# QREx16.net
KiCad netlist of a schematic drawn in EAGLE
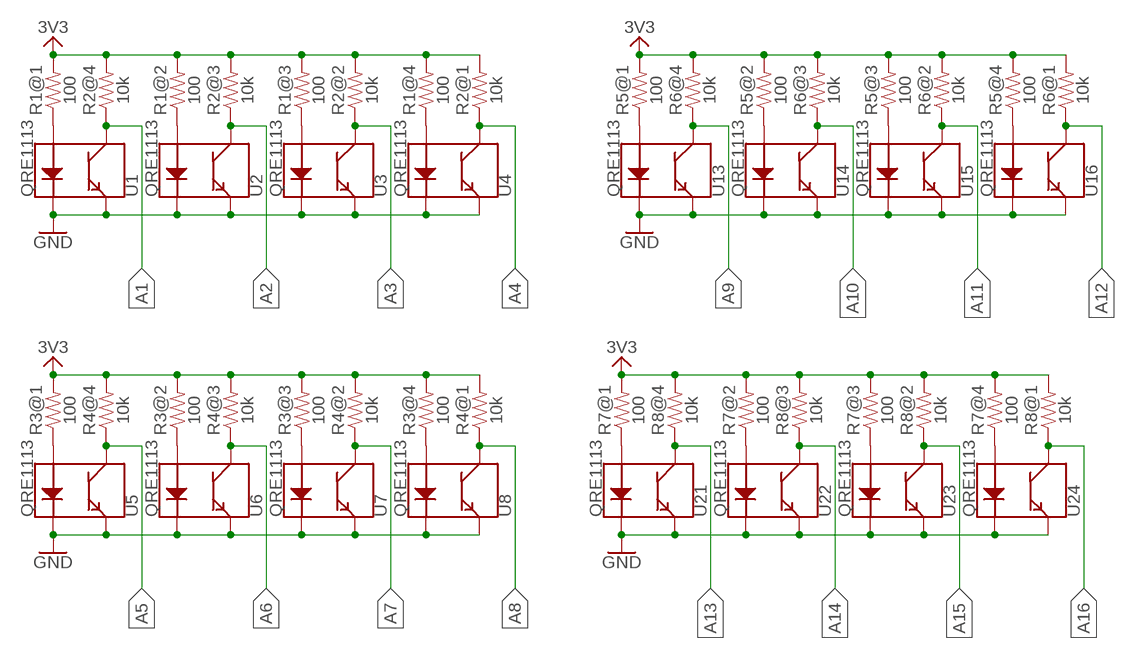
[diagram p0: schematic, sheet 1]

(export (version "E")
  (design (tool "Eeschema 10.0.6"))
  (components
    (comp (ref "R1")
      (value "100")
      (footprint "eagle-import:RESCAF80P320X160X60-8N")
      (libsource (lib "eagle-import") (part "RESISTOR_ARRAY_1206_SEPARATE"))
    )
    (comp (ref "R2")
      (value "10k")
      (footprint "eagle-import:RESCAF80P320X160X60-8N")
      (libsource (lib "eagle-import") (part "RESISTOR_ARRAY_1206_SEPARATE"))
    )
    (comp (ref "R3")
      (value "100")
      (footprint "eagle-import:RESCAF80P320X160X60-8N")
      (libsource (lib "eagle-import") (part "RESISTOR_ARRAY_1206_SEPARATE"))
    )
    (comp (ref "R4")
      (value "10k")
      (footprint "eagle-import:RESCAF80P320X160X60-8N")
      (libsource (lib "eagle-import") (part "RESISTOR_ARRAY_1206_SEPARATE"))
    )
    (comp (ref "R5")
      (value "100")
      (footprint "eagle-import:RESCAF80P320X160X60-8N")
      (libsource (lib "eagle-import") (part "RESISTOR_ARRAY_1206_SEPARATE"))
    )
    (comp (ref "R6")
      (value "10k")
      (footprint "eagle-import:RESCAF80P320X160X60-8N")
      (libsource (lib "eagle-import") (part "RESISTOR_ARRAY_1206_SEPARATE"))
    )
    (comp (ref "R7")
      (value "100")
      (footprint "eagle-import:RESCAF80P320X160X60-8N")
      (libsource (lib "eagle-import") (part "RESISTOR_ARRAY_1206_SEPARATE"))
    )
    (comp (ref "R8")
      (value "10k")
      (footprint "eagle-import:RESCAF80P320X160X60-8N")
      (libsource (lib "eagle-import") (part "RESISTOR_ARRAY_1206_SEPARATE"))
    )
    (comp (ref "U1")
      (value "QRE1113")
      (footprint "eagle-import:QRE1113-W")
      (libsource (lib "eagle-import") (part "QRE1113SMD-W"))
    )
    (comp (ref "U2")
      (value "QRE1113")
      (footprint "eagle-import:QRE1113-W")
      (libsource (lib "eagle-import") (part "QRE1113SMD-W"))
    )
    (comp (ref "U3")
      (value "QRE1113")
      (footprint "eagle-import:QRE1113-W")
      (libsource (lib "eagle-import") (part "QRE1113SMD-W"))
    )
    (comp (ref "U4")
      (value "QRE1113")
      (footprint "eagle-import:QRE1113-W")
      (libsource (lib "eagle-import") (part "QRE1113SMD-W"))
    )
    (comp (ref "U5")
      (value "QRE1113")
      (footprint "eagle-import:QRE1113-W")
      (libsource (lib "eagle-import") (part "QRE1113SMD-W"))
    )
    (comp (ref "U6")
      (value "QRE1113")
      (footprint "eagle-import:QRE1113-W")
      (libsource (lib "eagle-import") (part "QRE1113SMD-W"))
    )
    (comp (ref "U7")
      (value "QRE1113")
      (footprint "eagle-import:QRE1113-W")
      (libsource (lib "eagle-import") (part "QRE1113SMD-W"))
    )
    (comp (ref "U8")
      (value "QRE1113")
      (footprint "eagle-import:QRE1113-W")
      (libsource (lib "eagle-import") (part "QRE1113SMD-W"))
    )
    (comp (ref "U13")
      (value "QRE1113")
      (footprint "eagle-import:QRE1113-W")
      (libsource (lib "eagle-import") (part "QRE1113SMD-W"))
    )
    (comp (ref "U14")
      (value "QRE1113")
      (footprint "eagle-import:QRE1113-W")
      (libsource (lib "eagle-import") (part "QRE1113SMD-W"))
    )
    (comp (ref "U15")
      (value "QRE1113")
      (footprint "eagle-import:QRE1113-W")
      (libsource (lib "eagle-import") (part "QRE1113SMD-W"))
    )
    (comp (ref "U16")
      (value "QRE1113")
      (footprint "eagle-import:QRE1113-W")
      (libsource (lib "eagle-import") (part "QRE1113SMD-W"))
    )
    (comp (ref "U21")
      (value "QRE1113")
      (footprint "eagle-import:QRE1113-W")
      (libsource (lib "eagle-import") (part "QRE1113SMD-W"))
    )
    (comp (ref "U22")
      (value "QRE1113")
      (footprint "eagle-import:QRE1113-W")
      (libsource (lib "eagle-import") (part "QRE1113SMD-W"))
    )
    (comp (ref "U23")
      (value "QRE1113")
      (footprint "eagle-import:QRE1113-W")
      (libsource (lib "eagle-import") (part "QRE1113SMD-W"))
    )
    (comp (ref "U24")
      (value "QRE1113")
      (footprint "eagle-import:QRE1113-W")
      (libsource (lib "eagle-import") (part "QRE1113SMD-W"))
    )
  )
  (nets
    (net (code "1") (name "A1") (class "Default")
      (node (ref "R2") (pin "4") (pinfunction "1_4") (pintype "passive"))
      (node (ref "U1") (pin "3") (pinfunction "C_3") (pintype "bidirectional"))
    )
    (net (code "2") (name "A2") (class "Default")
      (node (ref "R2") (pin "3") (pinfunction "1_3") (pintype "passive"))
      (node (ref "U2") (pin "3") (pinfunction "C_3") (pintype "bidirectional"))
    )
    (net (code "3") (name "A3") (class "Default")
      (node (ref "R2") (pin "2") (pinfunction "1_2") (pintype "passive"))
      (node (ref "U3") (pin "3") (pinfunction "C_3") (pintype "bidirectional"))
    )
    (net (code "4") (name "A4") (class "Default")
      (node (ref "R2") (pin "1") (pinfunction "1_1") (pintype "passive"))
      (node (ref "U4") (pin "3") (pinfunction "C_3") (pintype "bidirectional"))
    )
    (net (code "5") (name "A5") (class "Default")
      (node (ref "R4") (pin "4") (pinfunction "1_4") (pintype "passive"))
      (node (ref "U5") (pin "3") (pinfunction "C_3") (pintype "bidirectional"))
    )
    (net (code "6") (name "A6") (class "Default")
      (node (ref "R4") (pin "3") (pinfunction "1_3") (pintype "passive"))
      (node (ref "U6") (pin "3") (pinfunction "C_3") (pintype "bidirectional"))
    )
    (net (code "7") (name "A7") (class "Default")
      (node (ref "R4") (pin "2") (pinfunction "1_2") (pintype "passive"))
      (node (ref "U7") (pin "3") (pinfunction "C_3") (pintype "bidirectional"))
    )
    (net (code "8") (name "A8") (class "Default")
      (node (ref "R4") (pin "1") (pinfunction "1_1") (pintype "passive"))
      (node (ref "U8") (pin "3") (pinfunction "C_3") (pintype "bidirectional"))
    )
    (net (code "9") (name "A9") (class "Default")
      (node (ref "R6") (pin "4") (pinfunction "1_4") (pintype "passive"))
      (node (ref "U13") (pin "3") (pinfunction "C_3") (pintype "bidirectional"))
    )
    (net (code "10") (name "A10") (class "Default")
      (node (ref "R6") (pin "3") (pinfunction "1_3") (pintype "passive"))
      (node (ref "U14") (pin "3") (pinfunction "C_3") (pintype "bidirectional"))
    )
    (net (code "11") (name "A11") (class "Default")
      (node (ref "R6") (pin "2") (pinfunction "1_2") (pintype "passive"))
      (node (ref "U15") (pin "3") (pinfunction "C_3") (pintype "bidirectional"))
    )
    (net (code "12") (name "A12") (class "Default")
      (node (ref "R6") (pin "1") (pinfunction "1_1") (pintype "passive"))
      (node (ref "U16") (pin "3") (pinfunction "C_3") (pintype "bidirectional"))
    )
    (net (code "13") (name "A13") (class "Default")
      (node (ref "R8") (pin "4") (pinfunction "1_4") (pintype "passive"))
      (node (ref "U21") (pin "3") (pinfunction "C_3") (pintype "bidirectional"))
    )
    (net (code "14") (name "A14") (class "Default")
      (node (ref "R8") (pin "3") (pinfunction "1_3") (pintype "passive"))
      (node (ref "U22") (pin "3") (pinfunction "C_3") (pintype "bidirectional"))
    )
    (net (code "15") (name "A15") (class "Default")
      (node (ref "R8") (pin "2") (pinfunction "1_2") (pintype "passive"))
      (node (ref "U23") (pin "3") (pinfunction "C_3") (pintype "bidirectional"))
    )
    (net (code "16") (name "A16") (class "Default")
      (node (ref "R8") (pin "1") (pinfunction "1_1") (pintype "passive"))
      (node (ref "U24") (pin "3") (pinfunction "C_3") (pintype "bidirectional"))
    )
    (net (code "17") (name "Net-(R1B-1)") (class "Default")
      (node (ref "R1") (pin "2") (pinfunction "1_2") (pintype "passive"))
      (node (ref "U2") (pin "1") (pinfunction "A_1") (pintype "bidirectional"))
    )
    (net (code "18") (name "Net-(R1C-1)") (class "Default")
      (node (ref "R1") (pin "3") (pinfunction "1_3") (pintype "passive"))
      (node (ref "U3") (pin "1") (pinfunction "A_1") (pintype "bidirectional"))
    )
    (net (code "19") (name "Net-(R1D-1)") (class "Default")
      (node (ref "R1") (pin "4") (pinfunction "1_4") (pintype "passive"))
      (node (ref "U4") (pin "1") (pinfunction "A_1") (pintype "bidirectional"))
    )
    (net (code "20") (name "Net-(R3B-1)") (class "Default")
      (node (ref "R3") (pin "2") (pinfunction "1_2") (pintype "passive"))
      (node (ref "U6") (pin "1") (pinfunction "A_1") (pintype "bidirectional"))
    )
    (net (code "21") (name "Net-(R3C-1)") (class "Default")
      (node (ref "R3") (pin "3") (pinfunction "1_3") (pintype "passive"))
      (node (ref "U7") (pin "1") (pinfunction "A_1") (pintype "bidirectional"))
    )
    (net (code "22") (name "Net-(R3D-1)") (class "Default")
      (node (ref "R3") (pin "4") (pinfunction "1_4") (pintype "passive"))
      (node (ref "U8") (pin "1") (pinfunction "A_1") (pintype "bidirectional"))
    )
    (net (code "23") (name "Net-(R5B-1)") (class "Default")
      (node (ref "R5") (pin "2") (pinfunction "1_2") (pintype "passive"))
      (node (ref "U14") (pin "1") (pinfunction "A_1") (pintype "bidirectional"))
    )
    (net (code "24") (name "Net-(R5C-1)") (class "Default")
      (node (ref "R5") (pin "3") (pinfunction "1_3") (pintype "passive"))
      (node (ref "U15") (pin "1") (pinfunction "A_1") (pintype "bidirectional"))
    )
    (net (code "25") (name "Net-(R5D-1)") (class "Default")
      (node (ref "R5") (pin "4") (pinfunction "1_4") (pintype "passive"))
      (node (ref "U16") (pin "1") (pinfunction "A_1") (pintype "bidirectional"))
    )
    (net (code "26") (name "Net-(R7B-1)") (class "Default")
      (node (ref "R7") (pin "2") (pinfunction "1_2") (pintype "passive"))
      (node (ref "U22") (pin "1") (pinfunction "A_1") (pintype "bidirectional"))
    )
    (net (code "27") (name "Net-(R7C-1)") (class "Default")
      (node (ref "R7") (pin "3") (pinfunction "1_3") (pintype "passive"))
      (node (ref "U23") (pin "1") (pinfunction "A_1") (pintype "bidirectional"))
    )
    (net (code "28") (name "Net-(R7D-1)") (class "Default")
      (node (ref "R7") (pin "4") (pinfunction "1_4") (pintype "passive"))
      (node (ref "U24") (pin "1") (pinfunction "A_1") (pintype "bidirectional"))
    )
    (net (code "29") (name "Net-(U1-A)") (class "Default")
      (node (ref "R1") (pin "1") (pinfunction "1_1") (pintype "passive"))
      (node (ref "U1") (pin "1") (pinfunction "A_1") (pintype "bidirectional"))
    )
    (net (code "30") (name "Net-(U5-A)") (class "Default")
      (node (ref "R3") (pin "1") (pinfunction "1_1") (pintype "passive"))
      (node (ref "U5") (pin "1") (pinfunction "A_1") (pintype "bidirectional"))
    )
    (net (code "31") (name "Net-(U13-A)") (class "Default")
      (node (ref "R5") (pin "1") (pinfunction "1_1") (pintype "passive"))
      (node (ref "U13") (pin "1") (pinfunction "A_1") (pintype "bidirectional"))
    )
    (net (code "32") (name "Net-(U21-A)") (class "Default")
      (node (ref "R7") (pin "1") (pinfunction "1_1") (pintype "passive"))
      (node (ref "U21") (pin "1") (pinfunction "A_1") (pintype "bidirectional"))
    )
    (net (code "33") (name "SUPPLY_3.3V") (class "Default")
      (node (ref "R1") (pin "5") (pinfunction "2_5") (pintype "passive"))
      (node (ref "R1") (pin "6") (pinfunction "2_6") (pintype "passive"))
      (node (ref "R1") (pin "7") (pinfunction "2_7") (pintype "passive"))
      (node (ref "R1") (pin "8") (pinfunction "2_8") (pintype "passive"))
      (node (ref "R2") (pin "5") (pinfunction "2_5") (pintype "passive"))
      (node (ref "R2") (pin "6") (pinfunction "2_6") (pintype "passive"))
      (node (ref "R2") (pin "7") (pinfunction "2_7") (pintype "passive"))
      (node (ref "R2") (pin "8") (pinfunction "2_8") (pintype "passive"))
      (node (ref "R3") (pin "5") (pinfunction "2_5") (pintype "passive"))
      (node (ref "R3") (pin "6") (pinfunction "2_6") (pintype "passive"))
      (node (ref "R3") (pin "7") (pinfunction "2_7") (pintype "passive"))
      (node (ref "R3") (pin "8") (pinfunction "2_8") (pintype "passive"))
      (node (ref "R4") (pin "5") (pinfunction "2_5") (pintype "passive"))
      (node (ref "R4") (pin "6") (pinfunction "2_6") (pintype "passive"))
      (node (ref "R4") (pin "7") (pinfunction "2_7") (pintype "passive"))
      (node (ref "R4") (pin "8") (pinfunction "2_8") (pintype "passive"))
      (node (ref "R5") (pin "5") (pinfunction "2_5") (pintype "passive"))
      (node (ref "R5") (pin "6") (pinfunction "2_6") (pintype "passive"))
      (node (ref "R5") (pin "7") (pinfunction "2_7") (pintype "passive"))
      (node (ref "R5") (pin "8") (pinfunction "2_8") (pintype "passive"))
      (node (ref "R6") (pin "5") (pinfunction "2_5") (pintype "passive"))
      (node (ref "R6") (pin "6") (pinfunction "2_6") (pintype "passive"))
      (node (ref "R6") (pin "7") (pinfunction "2_7") (pintype "passive"))
      (node (ref "R6") (pin "8") (pinfunction "2_8") (pintype "passive"))
      (node (ref "R7") (pin "5") (pinfunction "2_5") (pintype "passive"))
      (node (ref "R7") (pin "6") (pinfunction "2_6") (pintype "passive"))
      (node (ref "R7") (pin "7") (pinfunction "2_7") (pintype "passive"))
      (node (ref "R7") (pin "8") (pinfunction "2_8") (pintype "passive"))
      (node (ref "R8") (pin "5") (pinfunction "2_5") (pintype "passive"))
      (node (ref "R8") (pin "6") (pinfunction "2_6") (pintype "passive"))
      (node (ref "R8") (pin "7") (pinfunction "2_7") (pintype "passive"))
      (node (ref "R8") (pin "8") (pinfunction "2_8") (pintype "passive"))
    )
    (net (code "34") (name "SUPPLY_GND") (class "Default")
      (node (ref "U1") (pin "2") (pinfunction "K_2") (pintype "bidirectional"))
      (node (ref "U1") (pin "4") (pinfunction "E_4") (pintype "bidirectional"))
      (node (ref "U13") (pin "2") (pinfunction "K_2") (pintype "bidirectional"))
      (node (ref "U13") (pin "4") (pinfunction "E_4") (pintype "bidirectional"))
      (node (ref "U14") (pin "2") (pinfunction "K_2") (pintype "bidirectional"))
      (node (ref "U14") (pin "4") (pinfunction "E_4") (pintype "bidirectional"))
      (node (ref "U15") (pin "2") (pinfunction "K_2") (pintype "bidirectional"))
      (node (ref "U15") (pin "4") (pinfunction "E_4") (pintype "bidirectional"))
      (node (ref "U16") (pin "2") (pinfunction "K_2") (pintype "bidirectional"))
      (node (ref "U16") (pin "4") (pinfunction "E_4") (pintype "bidirectional"))
      (node (ref "U2") (pin "2") (pinfunction "K_2") (pintype "bidirectional"))
      (node (ref "U2") (pin "4") (pinfunction "E_4") (pintype "bidirectional"))
      (node (ref "U21") (pin "2") (pinfunction "K_2") (pintype "bidirectional"))
      (node (ref "U21") (pin "4") (pinfunction "E_4") (pintype "bidirectional"))
      (node (ref "U22") (pin "2") (pinfunction "K_2") (pintype "bidirectional"))
      (node (ref "U22") (pin "4") (pinfunction "E_4") (pintype "bidirectional"))
      (node (ref "U23") (pin "2") (pinfunction "K_2") (pintype "bidirectional"))
      (node (ref "U23") (pin "4") (pinfunction "E_4") (pintype "bidirectional"))
      (node (ref "U24") (pin "2") (pinfunction "K_2") (pintype "bidirectional"))
      (node (ref "U24") (pin "4") (pinfunction "E_4") (pintype "bidirectional"))
      (node (ref "U3") (pin "2") (pinfunction "K_2") (pintype "bidirectional"))
      (node (ref "U3") (pin "4") (pinfunction "E_4") (pintype "bidirectional"))
      (node (ref "U4") (pin "2") (pinfunction "K_2") (pintype "bidirectional"))
      (node (ref "U4") (pin "4") (pinfunction "E_4") (pintype "bidirectional"))
      (node (ref "U5") (pin "2") (pinfunction "K_2") (pintype "bidirectional"))
      (node (ref "U5") (pin "4") (pinfunction "E_4") (pintype "bidirectional"))
      (node (ref "U6") (pin "2") (pinfunction "K_2") (pintype "bidirectional"))
      (node (ref "U6") (pin "4") (pinfunction "E_4") (pintype "bidirectional"))
      (node (ref "U7") (pin "2") (pinfunction "K_2") (pintype "bidirectional"))
      (node (ref "U7") (pin "4") (pinfunction "E_4") (pintype "bidirectional"))
      (node (ref "U8") (pin "2") (pinfunction "K_2") (pintype "bidirectional"))
      (node (ref "U8") (pin "4") (pinfunction "E_4") (pintype "bidirectional"))
    )
  )
)
